# Philter.net
KiCad netlist of a schematic drawn in EAGLE
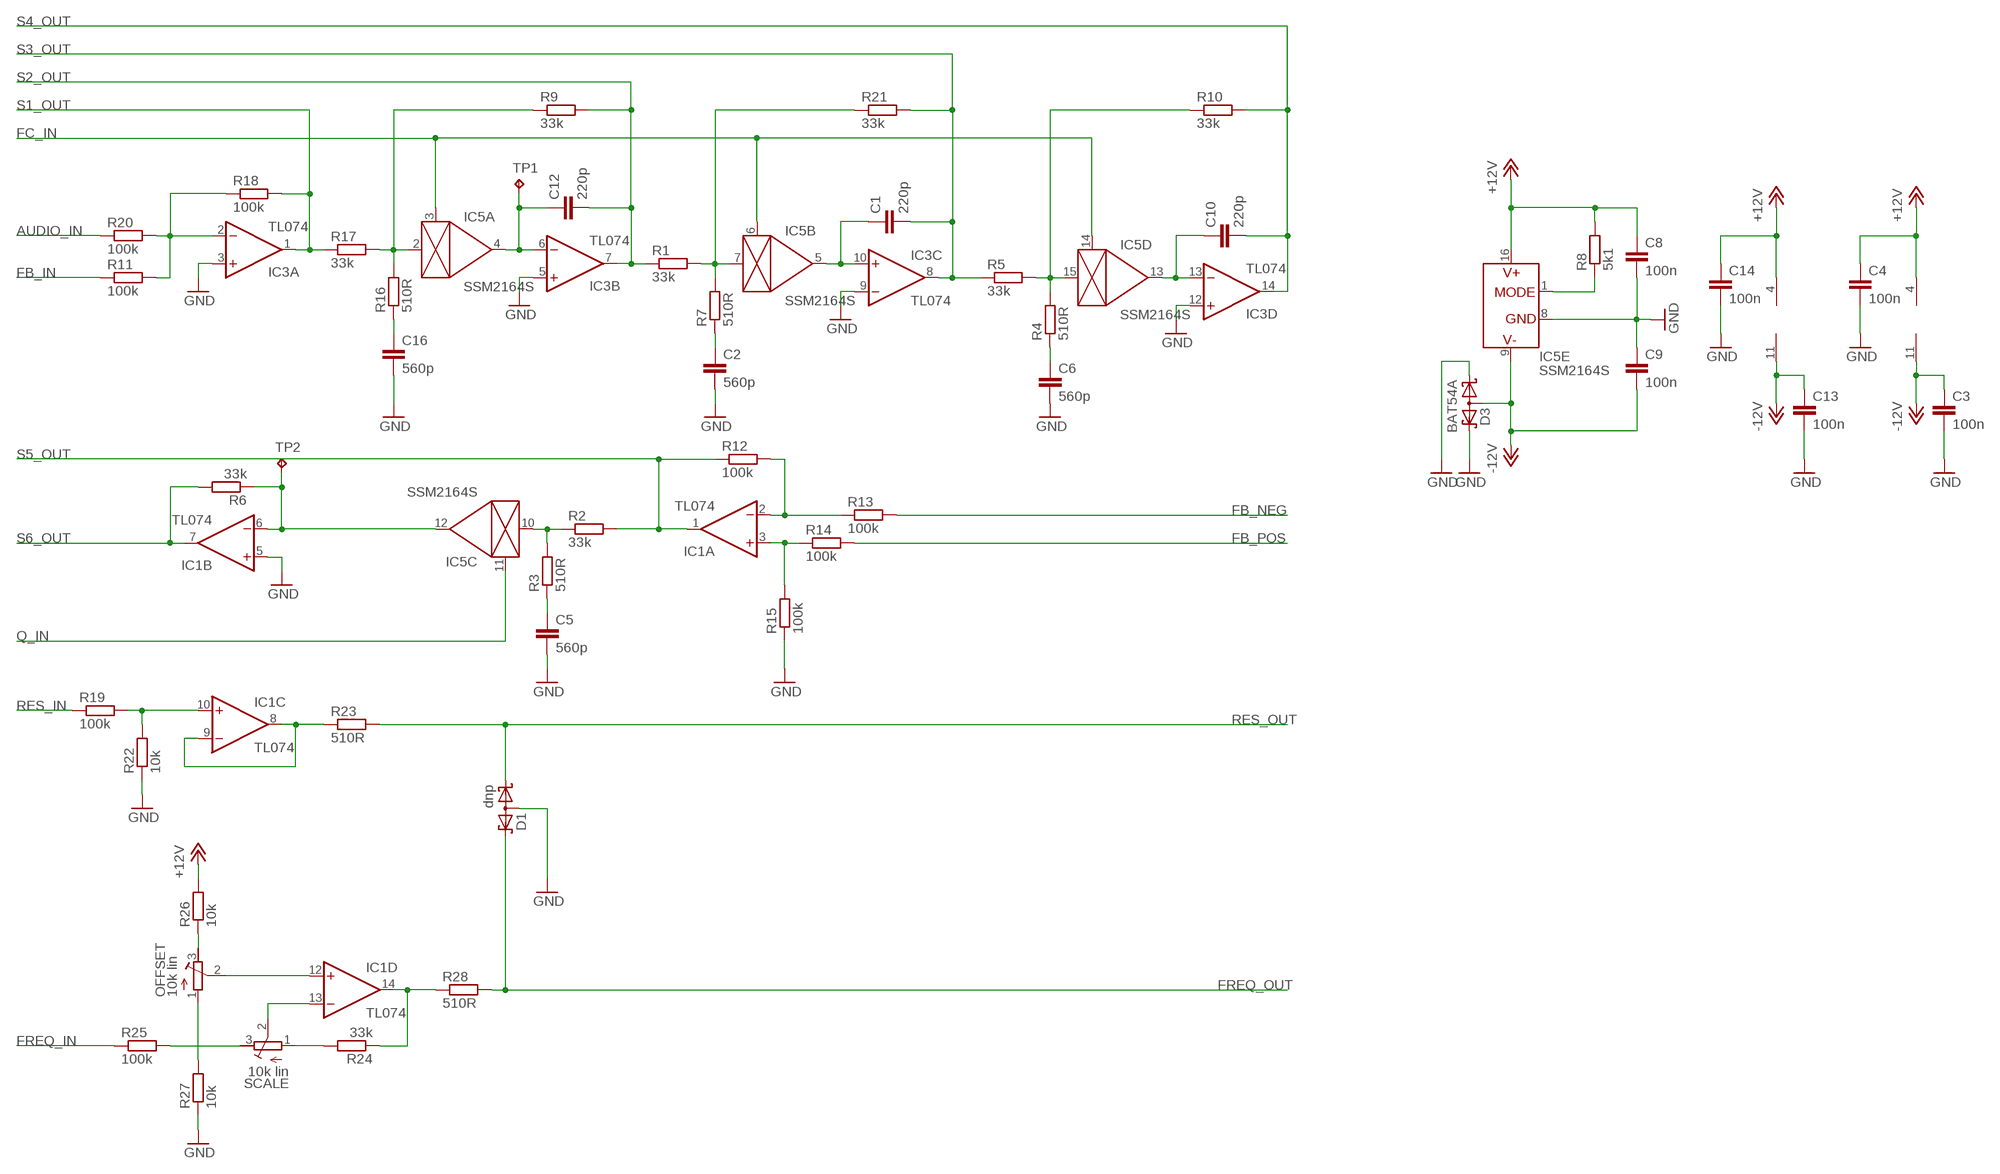
[diagram p0: schematic, sheet 1]

(export (version "E")
  (design (tool "Eeschema 10.0.6"))
  (components
    (comp (ref "C1")
      (value "220p")
      (footprint "eagle-import:C0603")
      (libsource (lib "eagle-import") (part "C-EUC0603"))
    )
    (comp (ref "C2")
      (value "560p")
      (footprint "eagle-import:C0603")
      (libsource (lib "eagle-import") (part "C-EUC0603"))
    )
    (comp (ref "C3")
      (value "100n")
      (footprint "eagle-import:C0603K")
      (libsource (lib "eagle-import") (part "C-EUC0603K"))
    )
    (comp (ref "C4")
      (value "100n")
      (footprint "eagle-import:C0603K")
      (libsource (lib "eagle-import") (part "C-EUC0603K"))
    )
    (comp (ref "C5")
      (value "560p")
      (footprint "eagle-import:C0603")
      (libsource (lib "eagle-import") (part "C-EUC0603"))
    )
    (comp (ref "C6")
      (value "560p")
      (footprint "eagle-import:C0603")
      (libsource (lib "eagle-import") (part "C-EUC0603"))
    )
    (comp (ref "C8")
      (value "100n")
      (footprint "eagle-import:C0603K")
      (libsource (lib "eagle-import") (part "C-EUC0603K"))
    )
    (comp (ref "C9")
      (value "100n")
      (footprint "eagle-import:C0603K")
      (libsource (lib "eagle-import") (part "C-EUC0603K"))
    )
    (comp (ref "C10")
      (value "220p")
      (footprint "eagle-import:C0603")
      (libsource (lib "eagle-import") (part "C-EUC0603"))
    )
    (comp (ref "C12")
      (value "220p")
      (footprint "eagle-import:C0603")
      (libsource (lib "eagle-import") (part "C-EUC0603"))
    )
    (comp (ref "C13")
      (value "100n")
      (footprint "eagle-import:C0603K")
      (libsource (lib "eagle-import") (part "C-EUC0603K"))
    )
    (comp (ref "C14")
      (value "100n")
      (footprint "eagle-import:C0603K")
      (libsource (lib "eagle-import") (part "C-EUC0603K"))
    )
    (comp (ref "C16")
      (value "560p")
      (footprint "eagle-import:C0603")
      (libsource (lib "eagle-import") (part "C-EUC0603"))
    )
    (comp (ref "D1")
      (value "dnp")
      (footprint "eagle-import:SOT23")
      (libsource (lib "eagle-import") (part "BAT54A"))
    )
    (comp (ref "D3")
      (value "BAT54A")
      (footprint "eagle-import:SOT23")
      (libsource (lib "eagle-import") (part "BAT54A"))
    )
    (comp (ref "IC1")
      (value "TL074")
      (footprint "eagle-import:SO14")
      (libsource (lib "eagle-import") (part "TL074D"))
    )
    (comp (ref "IC3")
      (value "TL074")
      (footprint "eagle-import:SO14")
      (libsource (lib "eagle-import") (part "TL074D"))
    )
    (comp (ref "IC5")
      (value "SSM2164S")
      (footprint "eagle-import:SOIC16N")
      (libsource (lib "eagle-import") (part "SSM2164S"))
    )
    (comp (ref "OFFSET")
      (value "10k lin")
      (footprint "eagle-import:RTRIM64W")
      (libsource (lib "eagle-import") (part "R-TRIMM64W"))
    )
    (comp (ref "R1")
      (value "33k")
      (footprint "eagle-import:0603")
      (libsource (lib "eagle-import") (part "R-EU_0603"))
    )
    (comp (ref "R2")
      (value "33k")
      (footprint "eagle-import:0603")
      (libsource (lib "eagle-import") (part "R-EU_0603"))
    )
    (comp (ref "R3")
      (value "510R")
      (footprint "eagle-import:0603")
      (libsource (lib "eagle-import") (part "R-EU_0603"))
    )
    (comp (ref "R4")
      (value "510R")
      (footprint "eagle-import:0603")
      (libsource (lib "eagle-import") (part "R-EU_0603"))
    )
    (comp (ref "R5")
      (value "33k")
      (footprint "eagle-import:0603")
      (libsource (lib "eagle-import") (part "R-EU_0603"))
    )
    (comp (ref "R6")
      (value "33k")
      (footprint "eagle-import:0603")
      (libsource (lib "eagle-import") (part "R-EU_0603"))
    )
    (comp (ref "R7")
      (value "510R")
      (footprint "eagle-import:0603")
      (libsource (lib "eagle-import") (part "R-EU_0603"))
    )
    (comp (ref "R8")
      (value "5k1")
      (footprint "eagle-import:0603")
      (libsource (lib "eagle-import") (part "R-EU_0603"))
    )
    (comp (ref "R9")
      (value "33k")
      (footprint "eagle-import:0603")
      (libsource (lib "eagle-import") (part "R-EU_0603"))
    )
    (comp (ref "R10")
      (value "33k")
      (footprint "eagle-import:0603")
      (libsource (lib "eagle-import") (part "R-EU_0603"))
    )
    (comp (ref "R11")
      (value "100k")
      (footprint "eagle-import:0603")
      (libsource (lib "eagle-import") (part "R-EU_0603"))
    )
    (comp (ref "R12")
      (value "100k")
      (footprint "eagle-import:0603")
      (libsource (lib "eagle-import") (part "R-EU_0603"))
    )
    (comp (ref "R13")
      (value "100k")
      (footprint "eagle-import:0603")
      (libsource (lib "eagle-import") (part "R-EU_0603"))
    )
    (comp (ref "R14")
      (value "100k")
      (footprint "eagle-import:0603")
      (libsource (lib "eagle-import") (part "R-EU_0603"))
    )
    (comp (ref "R15")
      (value "100k")
      (footprint "eagle-import:0603")
      (libsource (lib "eagle-import") (part "R-EU_0603"))
    )
    (comp (ref "R16")
      (value "510R")
      (footprint "eagle-import:0603")
      (libsource (lib "eagle-import") (part "R-EU_0603"))
    )
    (comp (ref "R17")
      (value "33k")
      (footprint "eagle-import:0603")
      (libsource (lib "eagle-import") (part "R-EU_0603"))
    )
    (comp (ref "R18")
      (value "100k")
      (footprint "eagle-import:0603")
      (libsource (lib "eagle-import") (part "R-EU_0603"))
    )
    (comp (ref "R19")
      (value "100k")
      (footprint "eagle-import:0603")
      (libsource (lib "eagle-import") (part "R-EU_0603"))
    )
    (comp (ref "R20")
      (value "100k")
      (footprint "eagle-import:0603")
      (libsource (lib "eagle-import") (part "R-EU_0603"))
    )
    (comp (ref "R21")
      (value "33k")
      (footprint "eagle-import:0603")
      (libsource (lib "eagle-import") (part "R-EU_0603"))
    )
    (comp (ref "R22")
      (value "10k")
      (footprint "eagle-import:0603")
      (libsource (lib "eagle-import") (part "R-EU_0603"))
    )
    (comp (ref "R23")
      (value "510R")
      (footprint "eagle-import:0603")
      (libsource (lib "eagle-import") (part "R-EU_0603"))
    )
    (comp (ref "R24")
      (value "33k")
      (footprint "eagle-import:0603")
      (libsource (lib "eagle-import") (part "R-EU_0603"))
    )
    (comp (ref "R25")
      (value "100k")
      (footprint "eagle-import:0603")
      (libsource (lib "eagle-import") (part "R-EU_0603"))
    )
    (comp (ref "R26")
      (value "10k")
      (footprint "eagle-import:0603")
      (libsource (lib "eagle-import") (part "R-EU_0603"))
    )
    (comp (ref "R27")
      (value "10k")
      (footprint "eagle-import:0603")
      (libsource (lib "eagle-import") (part "R-EU_0603"))
    )
    (comp (ref "R28")
      (value "510R")
      (footprint "eagle-import:0603")
      (libsource (lib "eagle-import") (part "R-EU_0603"))
    )
    (comp (ref "SCALE")
      (value "10k lin")
      (footprint "eagle-import:RTRIM64W")
      (libsource (lib "eagle-import") (part "R-TRIMM64W"))
    )
    (comp (ref "TP1")
      (value "TPPAD1-13")
      (footprint "eagle-import:P1-13")
      (libsource (lib "eagle-import") (part "TPPAD1-13"))
    )
    (comp (ref "TP2")
      (value "TPPAD1-13")
      (footprint "eagle-import:P1-13")
      (libsource (lib "eagle-import") (part "TPPAD1-13"))
    )
  )
  (nets
    (net (code "1") (name "+12V") (class "Default")
      (node (ref "C14") (pin "1") (pinfunction "1_1") (pintype "passive"))
      (node (ref "C4") (pin "1") (pinfunction "1_1") (pintype "passive"))
      (node (ref "C8") (pin "1") (pinfunction "1_1") (pintype "passive"))
      (node (ref "IC1") (pin "4") (pinfunction "V+_4") (pintype "power_in"))
      (node (ref "IC3") (pin "4") (pinfunction "V+_4") (pintype "power_in"))
      (node (ref "IC5") (pin "16") (pinfunction "V+_16") (pintype "power_in"))
      (node (ref "R26") (pin "2") (pinfunction "2_2") (pintype "passive"))
      (node (ref "R8") (pin "2") (pinfunction "2_2") (pintype "passive"))
    )
    (net (code "2") (name "-12V") (class "Default")
      (node (ref "C13") (pin "1") (pinfunction "1_1") (pintype "passive"))
      (node (ref "C3") (pin "1") (pinfunction "1_1") (pintype "passive"))
      (node (ref "C9") (pin "2") (pinfunction "2_2") (pintype "passive"))
      (node (ref "D3") (pin "3") (pinfunction "AA_3") (pintype "passive"))
      (node (ref "IC1") (pin "11") (pinfunction "V-_11") (pintype "power_in"))
      (node (ref "IC3") (pin "11") (pinfunction "V-_11") (pintype "power_in"))
      (node (ref "IC5") (pin "9") (pinfunction "V-_9") (pintype "power_in"))
    )
    (net (code "3") (name "/AUDIO_IN") (class "Default")
      (node (ref "R20") (pin "1") (pinfunction "1_1") (pintype "passive"))
    )
    (net (code "4") (name "/FB_IN") (class "Default")
      (node (ref "R11") (pin "1") (pinfunction "1_1") (pintype "passive"))
    )
    (net (code "5") (name "/FB_NEG") (class "Default")
      (node (ref "R13") (pin "2") (pinfunction "2_2") (pintype "passive"))
    )
    (net (code "6") (name "/FB_POS") (class "Default")
      (node (ref "R14") (pin "2") (pinfunction "2_2") (pintype "passive"))
    )
    (net (code "7") (name "/FC_IN") (class "Default")
      (node (ref "IC5") (pin "14") (pinfunction "CTRL_14") (pintype "input"))
      (node (ref "IC5") (pin "3") (pinfunction "CTRL_3") (pintype "input"))
      (node (ref "IC5") (pin "6") (pinfunction "CTRL_6") (pintype "input"))
    )
    (net (code "8") (name "/FREQ_IN") (class "Default")
      (node (ref "R25") (pin "1") (pinfunction "1_1") (pintype "passive"))
    )
    (net (code "9") (name "/FREQ_OUT") (class "Default")
      (node (ref "D1") (pin "2") (pinfunction "K2_2") (pintype "passive"))
      (node (ref "R28") (pin "2") (pinfunction "2_2") (pintype "passive"))
    )
    (net (code "10") (name "/Q_IN") (class "Default")
      (node (ref "IC5") (pin "11") (pinfunction "CTRL_11") (pintype "input"))
    )
    (net (code "11") (name "/RES_IN") (class "Default")
      (node (ref "R19") (pin "1") (pinfunction "1_1") (pintype "passive"))
    )
    (net (code "12") (name "/RES_OUT") (class "Default")
      (node (ref "D1") (pin "1") (pinfunction "K1_1") (pintype "passive"))
      (node (ref "R23") (pin "2") (pinfunction "2_2") (pintype "passive"))
    )
    (net (code "13") (name "/S1_OUT") (class "Default")
      (node (ref "IC3") (pin "1") (pinfunction "OUT_1") (pintype "output"))
      (node (ref "R17") (pin "1") (pinfunction "1_1") (pintype "passive"))
      (node (ref "R18") (pin "2") (pinfunction "2_2") (pintype "passive"))
    )
    (net (code "14") (name "/S2_OUT") (class "Default")
      (node (ref "C12") (pin "2") (pinfunction "2_2") (pintype "passive"))
      (node (ref "IC3") (pin "7") (pinfunction "OUT_7") (pintype "output"))
      (node (ref "R1") (pin "1") (pinfunction "1_1") (pintype "passive"))
      (node (ref "R9") (pin "2") (pinfunction "2_2") (pintype "passive"))
    )
    (net (code "15") (name "/S3_OUT") (class "Default")
      (node (ref "C1") (pin "2") (pinfunction "2_2") (pintype "passive"))
      (node (ref "IC3") (pin "8") (pinfunction "OUT_8") (pintype "output"))
      (node (ref "R21") (pin "2") (pinfunction "2_2") (pintype "passive"))
      (node (ref "R5") (pin "1") (pinfunction "1_1") (pintype "passive"))
    )
    (net (code "16") (name "/S4_OUT") (class "Default")
      (node (ref "C10") (pin "2") (pinfunction "2_2") (pintype "passive"))
      (node (ref "IC3") (pin "14") (pinfunction "OUT_14") (pintype "output"))
      (node (ref "R10") (pin "2") (pinfunction "2_2") (pintype "passive"))
    )
    (net (code "17") (name "/S5_OUT") (class "Default")
      (node (ref "IC1") (pin "1") (pinfunction "OUT_1") (pintype "output"))
      (node (ref "R12") (pin "1") (pinfunction "1_1") (pintype "passive"))
      (node (ref "R2") (pin "2") (pinfunction "2_2") (pintype "passive"))
    )
    (net (code "18") (name "/S6_OUT") (class "Default")
      (node (ref "IC1") (pin "7") (pinfunction "OUT_7") (pintype "output"))
      (node (ref "R6") (pin "2") (pinfunction "2_2") (pintype "passive"))
    )
    (net (code "19") (name "GND") (class "Default")
      (node (ref "C13") (pin "2") (pinfunction "2_2") (pintype "passive"))
      (node (ref "C14") (pin "2") (pinfunction "2_2") (pintype "passive"))
      (node (ref "C16") (pin "2") (pinfunction "2_2") (pintype "passive"))
      (node (ref "C2") (pin "2") (pinfunction "2_2") (pintype "passive"))
      (node (ref "C3") (pin "2") (pinfunction "2_2") (pintype "passive"))
      (node (ref "C4") (pin "2") (pinfunction "2_2") (pintype "passive"))
      (node (ref "C5") (pin "2") (pinfunction "2_2") (pintype "passive"))
      (node (ref "C6") (pin "2") (pinfunction "2_2") (pintype "passive"))
      (node (ref "C8") (pin "2") (pinfunction "2_2") (pintype "passive"))
      (node (ref "C9") (pin "1") (pinfunction "1_1") (pintype "passive"))
      (node (ref "D1") (pin "3") (pinfunction "AA_3") (pintype "passive"))
      (node (ref "D3") (pin "1") (pinfunction "K1_1") (pintype "passive"))
      (node (ref "D3") (pin "2") (pinfunction "K2_2") (pintype "passive"))
      (node (ref "IC1") (pin "5") (pinfunction "+IN_5") (pintype "input"))
      (node (ref "IC3") (pin "12") (pinfunction "+IN_12") (pintype "input"))
      (node (ref "IC3") (pin "3") (pinfunction "+IN_3") (pintype "input"))
      (node (ref "IC3") (pin "5") (pinfunction "+IN_5") (pintype "input"))
      (node (ref "IC3") (pin "9") (pinfunction "-IN_9") (pintype "input"))
      (node (ref "IC5") (pin "8") (pinfunction "GND_8") (pintype "power_in"))
      (node (ref "R15") (pin "1") (pinfunction "1_1") (pintype "passive"))
      (node (ref "R22") (pin "1") (pinfunction "1_1") (pintype "passive"))
      (node (ref "R27") (pin "1") (pinfunction "1_1") (pintype "passive"))
    )
    (net (code "20") (name "Net-(C2-Pad1)") (class "Default")
      (node (ref "C2") (pin "1") (pinfunction "1_1") (pintype "passive"))
      (node (ref "R7") (pin "1") (pinfunction "1_1") (pintype "passive"))
    )
    (net (code "21") (name "Net-(C5-Pad1)") (class "Default")
      (node (ref "C5") (pin "1") (pinfunction "1_1") (pintype "passive"))
      (node (ref "R3") (pin "1") (pinfunction "1_1") (pintype "passive"))
    )
    (net (code "22") (name "Net-(C6-Pad1)") (class "Default")
      (node (ref "C6") (pin "1") (pinfunction "1_1") (pintype "passive"))
      (node (ref "R4") (pin "1") (pinfunction "1_1") (pintype "passive"))
    )
    (net (code "23") (name "Net-(C16-Pad1)") (class "Default")
      (node (ref "C16") (pin "1") (pinfunction "1_1") (pintype "passive"))
      (node (ref "R16") (pin "1") (pinfunction "1_1") (pintype "passive"))
    )
    (net (code "24") (name "Net-(IC1A-+IN)") (class "Default")
      (node (ref "IC1") (pin "3") (pinfunction "+IN_3") (pintype "input"))
      (node (ref "R14") (pin "1") (pinfunction "1_1") (pintype "passive"))
      (node (ref "R15") (pin "2") (pinfunction "2_2") (pintype "passive"))
    )
    (net (code "25") (name "Net-(IC1A--IN)") (class "Default")
      (node (ref "IC1") (pin "2") (pinfunction "-IN_2") (pintype "input"))
      (node (ref "R12") (pin "2") (pinfunction "2_2") (pintype "passive"))
      (node (ref "R13") (pin "1") (pinfunction "1_1") (pintype "passive"))
    )
    (net (code "26") (name "Net-(IC1B--IN)") (class "Default")
      (node (ref "IC1") (pin "6") (pinfunction "-IN_6") (pintype "input"))
      (node (ref "IC5") (pin "12") (pinfunction "OUT_12") (pintype "output"))
      (node (ref "R6") (pin "1") (pinfunction "1_1") (pintype "passive"))
      (node (ref "TP2") (pin "TP") (pinfunction "TP_TP") (pintype "input"))
    )
    (net (code "27") (name "Net-(IC1C-+IN)") (class "Default")
      (node (ref "IC1") (pin "10") (pinfunction "+IN_10") (pintype "input"))
      (node (ref "R19") (pin "2") (pinfunction "2_2") (pintype "passive"))
      (node (ref "R22") (pin "2") (pinfunction "2_2") (pintype "passive"))
    )
    (net (code "28") (name "Net-(IC1C--IN)") (class "Default")
      (node (ref "IC1") (pin "8") (pinfunction "OUT_8") (pintype "output"))
      (node (ref "IC1") (pin "9") (pinfunction "-IN_9") (pintype "input"))
      (node (ref "R23") (pin "1") (pinfunction "1_1") (pintype "passive"))
    )
    (net (code "29") (name "Net-(IC1D-+IN)") (class "Default")
      (node (ref "IC1") (pin "12") (pinfunction "+IN_12") (pintype "input"))
      (node (ref "OFFSET") (pin "2") (pinfunction "S_2") (pintype "passive"))
    )
    (net (code "30") (name "Net-(IC1D--IN)") (class "Default")
      (node (ref "IC1") (pin "13") (pinfunction "-IN_13") (pintype "input"))
      (node (ref "SCALE") (pin "2") (pinfunction "S_2") (pintype "passive"))
    )
    (net (code "31") (name "Net-(IC1D-OUT)") (class "Default")
      (node (ref "IC1") (pin "14") (pinfunction "OUT_14") (pintype "output"))
      (node (ref "R24") (pin "1") (pinfunction "1_1") (pintype "passive"))
      (node (ref "R28") (pin "1") (pinfunction "1_1") (pintype "passive"))
    )
    (net (code "32") (name "Net-(IC3A--IN)") (class "Default")
      (node (ref "IC3") (pin "2") (pinfunction "-IN_2") (pintype "input"))
      (node (ref "R11") (pin "2") (pinfunction "2_2") (pintype "passive"))
      (node (ref "R18") (pin "1") (pinfunction "1_1") (pintype "passive"))
      (node (ref "R20") (pin "2") (pinfunction "2_2") (pintype "passive"))
    )
    (net (code "33") (name "Net-(IC3B--IN)") (class "Default")
      (node (ref "C12") (pin "1") (pinfunction "1_1") (pintype "passive"))
      (node (ref "IC3") (pin "6") (pinfunction "-IN_6") (pintype "input"))
      (node (ref "IC5") (pin "4") (pinfunction "OUT_4") (pintype "output"))
      (node (ref "TP1") (pin "TP") (pinfunction "TP_TP") (pintype "input"))
    )
    (net (code "34") (name "Net-(IC3C-+IN)") (class "Default")
      (node (ref "C1") (pin "1") (pinfunction "1_1") (pintype "passive"))
      (node (ref "IC3") (pin "10") (pinfunction "+IN_10") (pintype "input"))
      (node (ref "IC5") (pin "5") (pinfunction "OUT_5") (pintype "output"))
    )
    (net (code "35") (name "Net-(IC3D--IN)") (class "Default")
      (node (ref "C10") (pin "1") (pinfunction "1_1") (pintype "passive"))
      (node (ref "IC3") (pin "13") (pinfunction "-IN_13") (pintype "input"))
      (node (ref "IC5") (pin "13") (pinfunction "OUT_13") (pintype "output"))
    )
    (net (code "36") (name "Net-(IC5A-IN)") (class "Default")
      (node (ref "IC5") (pin "2") (pinfunction "IN_2") (pintype "input"))
      (node (ref "R16") (pin "2") (pinfunction "2_2") (pintype "passive"))
      (node (ref "R17") (pin "2") (pinfunction "2_2") (pintype "passive"))
      (node (ref "R9") (pin "1") (pinfunction "1_1") (pintype "passive"))
    )
    (net (code "37") (name "Net-(IC5B-IN)") (class "Default")
      (node (ref "IC5") (pin "7") (pinfunction "IN_7") (pintype "input"))
      (node (ref "R1") (pin "2") (pinfunction "2_2") (pintype "passive"))
      (node (ref "R21") (pin "1") (pinfunction "1_1") (pintype "passive"))
      (node (ref "R7") (pin "2") (pinfunction "2_2") (pintype "passive"))
    )
    (net (code "38") (name "Net-(IC5C-IN)") (class "Default")
      (node (ref "IC5") (pin "10") (pinfunction "IN_10") (pintype "input"))
      (node (ref "R2") (pin "1") (pinfunction "1_1") (pintype "passive"))
      (node (ref "R3") (pin "2") (pinfunction "2_2") (pintype "passive"))
    )
    (net (code "39") (name "Net-(IC5D-IN)") (class "Default")
      (node (ref "IC5") (pin "15") (pinfunction "IN_15") (pintype "input"))
      (node (ref "R10") (pin "1") (pinfunction "1_1") (pintype "passive"))
      (node (ref "R4") (pin "2") (pinfunction "2_2") (pintype "passive"))
      (node (ref "R5") (pin "2") (pinfunction "2_2") (pintype "passive"))
    )
    (net (code "40") (name "Net-(IC5E-MODE)") (class "Default")
      (node (ref "IC5") (pin "1") (pinfunction "MODE_1") (pintype "input"))
      (node (ref "R8") (pin "1") (pinfunction "1_1") (pintype "passive"))
    )
    (net (code "41") (name "Net-(OFFSET-A)") (class "Default")
      (node (ref "OFFSET") (pin "1") (pinfunction "A_1") (pintype "passive"))
      (node (ref "R27") (pin "2") (pinfunction "2_2") (pintype "passive"))
    )
    (net (code "42") (name "Net-(OFFSET-E)") (class "Default")
      (node (ref "OFFSET") (pin "3") (pinfunction "E_3") (pintype "passive"))
      (node (ref "R26") (pin "1") (pinfunction "1_1") (pintype "passive"))
    )
    (net (code "43") (name "Net-(SCALE-A)") (class "Default")
      (node (ref "R24") (pin "2") (pinfunction "2_2") (pintype "passive"))
      (node (ref "SCALE") (pin "1") (pinfunction "A_1") (pintype "passive"))
    )
    (net (code "44") (name "Net-(SCALE-E)") (class "Default")
      (node (ref "R25") (pin "2") (pinfunction "2_2") (pintype "passive"))
      (node (ref "SCALE") (pin "3") (pinfunction "E_3") (pintype "passive"))
    )
  )
)
